# IO_FMU3_REV_C.net
KiCad netlist of a schematic drawn in Altium Designer
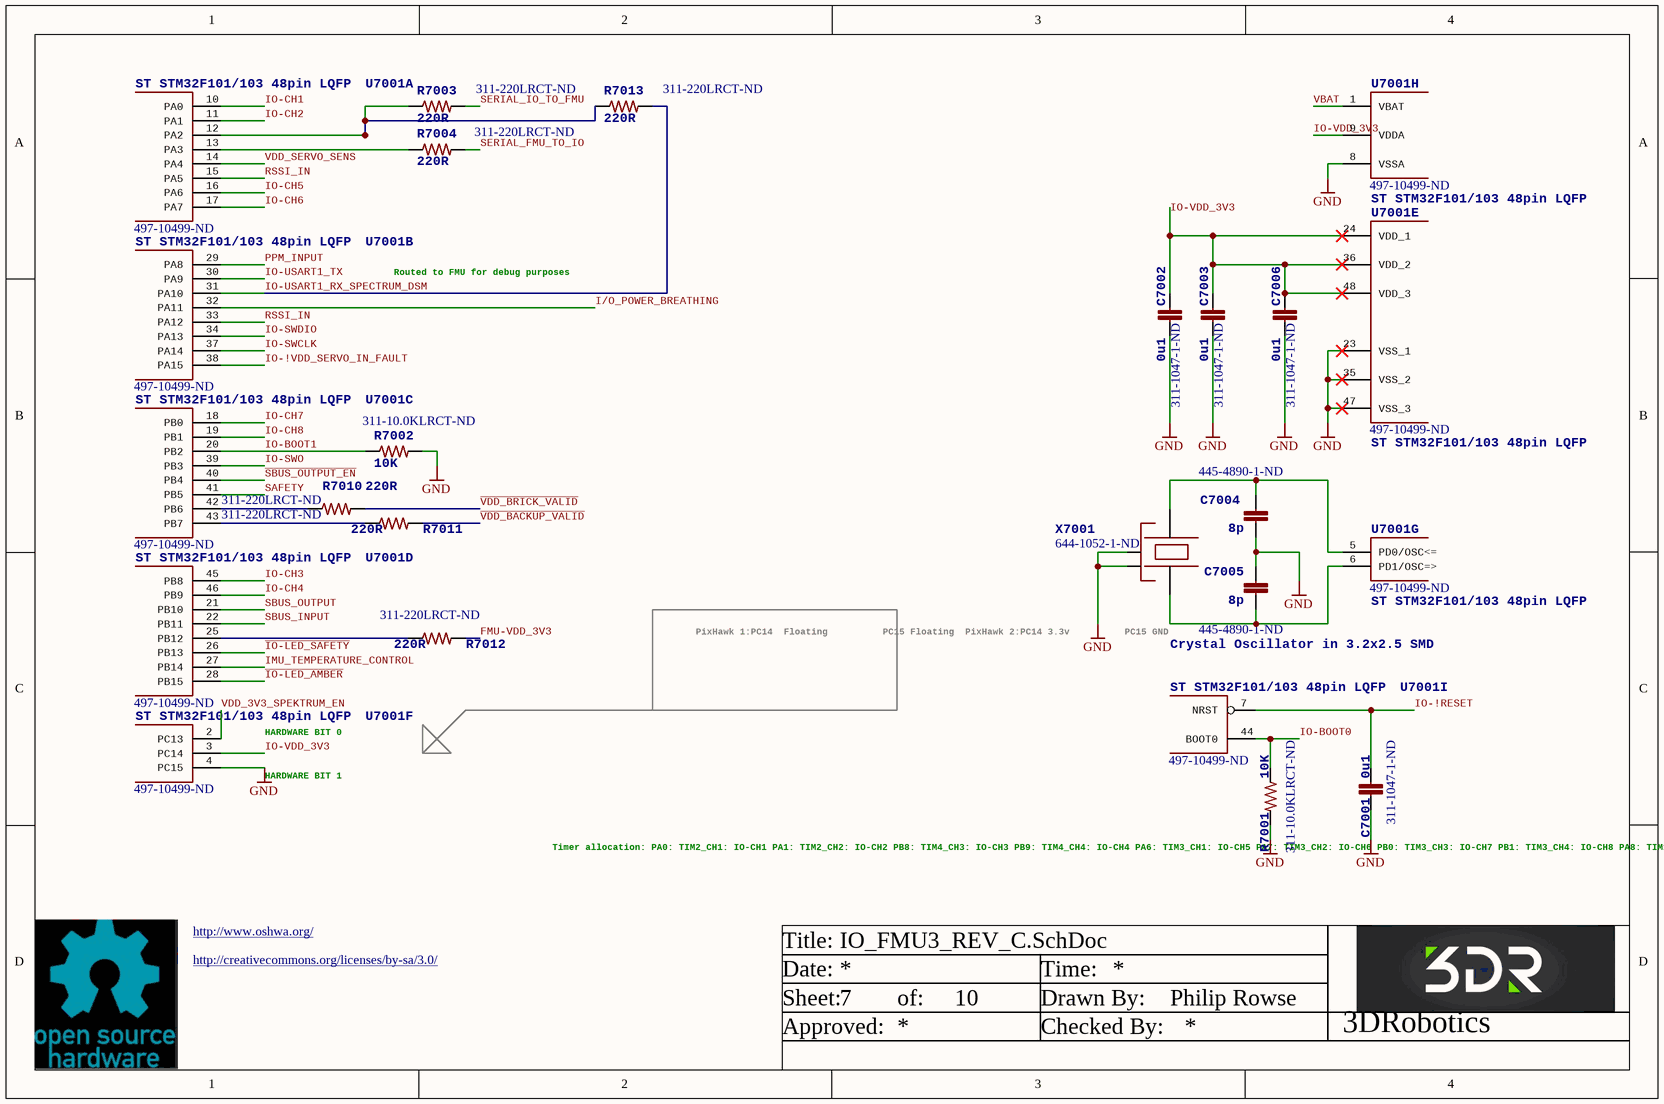
[diagram p0: IO_FMU3_REV_C.SchDoc]

(export (version "E")
  (design (tool "Eeschema 10.0.6"))
  (components
    (comp (ref "C7001")
      (value "0u1")
      (footprint "0402-CAP")
      (description "CAP CER 0.1UF 16V Y5V 0402")
      (fields
        (field (name "PARTNO") "CC0402ZRY5V7BB104")
        (field (name "SUPPLIER PART NUMBER 1") "311-1047-1-ND")
        (field (name "3DR_PARTNO") "ECM0700")
      )
      (libsource (lib "") (part "CAP0402_1"))
    )
    (comp (ref "C7002")
      (value "0u1")
      (footprint "0402-CAP")
      (description "CAP CER 0.1UF 16V Y5V 0402")
      (fields
        (field (name "PARTNO") "CC0402ZRY5V7BB104")
        (field (name "SUPPLIER PART NUMBER 1") "311-1047-1-ND")
        (field (name "3DR_PARTNO") "ECM0700")
      )
      (libsource (lib "pixhawk2") (part "CAP0402"))
    )
    (comp (ref "C7003")
      (value "0u1")
      (footprint "0402-CAP")
      (description "CAP CER 0.1UF 16V Y5V 0402")
      (fields
        (field (name "PARTNO") "CC0402ZRY5V7BB104")
        (field (name "SUPPLIER PART NUMBER 1") "311-1047-1-ND")
        (field (name "3DR_PARTNO") "ECM0700")
      )
      (libsource (lib "pixhawk2") (part "CAP0402"))
    )
    (comp (ref "C7004")
      (value "8p")
      (footprint "0402-CAP")
      (description "CAP CER 8PF 50V C0G 0402")
      (fields
        (field (name "PARTNO") "C1005C0G1H080C")
        (field (name "SUPPLIER PART NUMBER 1") "445-4890-1-ND")
        (field (name "3DR_PARTNO") "ECM0710")
      )
      (libsource (lib "pixhawk2") (part "CAP0402"))
    )
    (comp (ref "C7005")
      (value "8p")
      (footprint "0402-CAP")
      (description "CAP CER 8PF 50V C0G 0402")
      (fields
        (field (name "PARTNO") "C1005C0G1H080C")
        (field (name "SUPPLIER PART NUMBER 1") "445-4890-1-ND")
        (field (name "3DR_PARTNO") "ECM0710")
      )
      (libsource (lib "pixhawk2") (part "CAP0402"))
    )
    (comp (ref "C7006")
      (value "0u1")
      (footprint "0402-CAP")
      (description "CAP CER 0.1UF 16V Y5V 0402")
      (fields
        (field (name "PARTNO") "CC0402ZRY5V7BB104")
        (field (name "SUPPLIER PART NUMBER 1") "311-1047-1-ND")
        (field (name "3DR_PARTNO") "ECM0700")
      )
      (libsource (lib "pixhawk2") (part "CAP0402"))
    )
    (comp (ref "R7001")
      (value "10K")
      (footprint "0402-RES")
      (description "RES 10K OHM 1/16W 1% 0402 SMD")
      (fields
        (field (name "PARTNO") "RC0402FR-0710KL")
        (field (name "SUPPLIER PART NUMBER 1") "311-10.0KLRCT-ND")
        (field (name "3DR_PARTNO") "ECM0800")
      )
      (libsource (lib "pixhawk2") (part "RESISTOR0402-RES"))
    )
    (comp (ref "R7002")
      (value "10K")
      (footprint "0402-RES")
      (description "RES 10K OHM 1/16W 1% 0402 SMD")
      (fields
        (field (name "PARTNO") "RC0402FR-0710KL")
        (field (name "SUPPLIER PART NUMBER 1") "311-10.0KLRCT-ND")
        (field (name "3DR_PARTNO") "ECM0800")
      )
      (libsource (lib "pixhawk2") (part "RESISTOR0402-RES"))
    )
    (comp (ref "R7003")
      (value "220R")
      (footprint "0402-RES")
      (description "RES 220 OHM 1/16W 1% 0402 SMD")
      (fields
        (field (name "PARTNO") "RC0402FR-07220RL")
        (field (name "SUPPLIER PART NUMBER 1") "311-220LRCT-ND")
        (field (name "3DR_PARTNO") "ECM0821")
      )
      (libsource (lib "pixhawk2") (part "RESISTOR0402-RES"))
    )
    (comp (ref "R7004")
      (value "220R")
      (footprint "0402-RES")
      (description "RES 220 OHM 1/16W 1% 0402 SMD")
      (fields
        (field (name "PARTNO") "RC0402FR-07220RL")
        (field (name "SUPPLIER PART NUMBER 1") "311-220LRCT-ND")
        (field (name "3DR_PARTNO") "ECM0821")
      )
      (libsource (lib "pixhawk2") (part "RESISTOR0402-RES"))
    )
    (comp (ref "R7010")
      (value "220R")
      (footprint "0402-RES")
      (description "RES 220 OHM 1/16W 1% 0402 SMD")
      (fields
        (field (name "PARTNO") "RC0402FR-07220RL")
        (field (name "SUPPLIER PART NUMBER 1") "311-220LRCT-ND")
        (field (name "3DR_PARTNO") "ECM0821")
      )
      (libsource (lib "pixhawk2") (part "RESISTOR0402-RES"))
    )
    (comp (ref "R7011")
      (value "220R")
      (footprint "0402-RES")
      (description "RES 220 OHM 1/16W 1% 0402 SMD")
      (fields
        (field (name "PARTNO") "RC0402FR-07220RL")
        (field (name "SUPPLIER PART NUMBER 1") "311-220LRCT-ND")
        (field (name "3DR_PARTNO") "ECM0821")
      )
      (libsource (lib "pixhawk2") (part "RESISTOR0402-RES"))
    )
    (comp (ref "R7012")
      (value "220R")
      (footprint "0402-RES")
      (description "RES 220 OHM 1/16W 1% 0402 SMD")
      (fields
        (field (name "PARTNO") "RC0402FR-07220RL")
        (field (name "SUPPLIER PART NUMBER 1") "311-220LRCT-ND")
        (field (name "3DR_PARTNO") "ECM0821")
      )
      (libsource (lib "pixhawk2") (part "RESISTOR0402-RES"))
    )
    (comp (ref "R7013")
      (value "220R")
      (footprint "0402-RES")
      (description "RES 220 OHM 1/16W 1% 0402 SMD")
      (fields
        (field (name "PARTNO") "RC0402FR-07220RL")
        (field (name "SUPPLIER PART NUMBER 1") "311-220LRCT-ND")
        (field (name "3DR_PARTNO") "ECM0821")
      )
      (libsource (lib "pixhawk2") (part "RESISTOR0402-RES"))
    )
    (comp (ref "U7001")
      (value "ST STM32F101/103 48pin LQFP")
      (footprint "TQFP48")
      (description "MCU 32BIT ARM 64K FLASH 48LQFP")
      (fields (field (name "SUPPLIER PART NUMBER 1") "497-10499-ND") (field (name "3DR_PARTNO") "EMC0842"))
      (libsource (lib "pixhawk2") (part "STM32F10XCXT6"))
    )
    (comp (ref "X7001")
      (value "Crystal Oscillator in 3.2x2.5 SMD")
      (footprint "OSCILLATOR-3.2X2.5")
      (description "CRYSTAL 24MHZ 8PF SMD")
      (fields
        (field (name "SUPPLIER PART NUMBER 1") "644-1052-1-ND")
        (field (name "3DR_PARTNO") "ECM0708")
        (field (name "PARTNO") "NX3225SA-24.000MHZ-STD-CSR-1")
      )
      (libsource (lib "pixhawk2") (part "OSCILLATOR-3.2X2.5"))
    )
  )
  (nets
    (net (code "1") (name "/FMU-VDD_3V3") (class "Default")
      (node (ref "R7012") (pin "P$2") (pinfunction "2_P$2") (pintype "passive"))
    )
    (net (code "2") (name "/IMU_TEMPERATURE_CONTROL") (class "Default")
      (node (ref "U7001") (pin "27") (pinfunction "PB14_27") (pintype "passive"))
    )
    (net (code "3") (name "/IO-!RESET") (class "Default")
      (node (ref "C7001") (pin "P$2") (pinfunction "2_P$2") (pintype "passive"))
      (node (ref "U7001") (pin "7") (pinfunction "NRST_7") (pintype "passive"))
    )
    (net (code "4") (name "/IO-!VDD_SERVO_IN_FAULT") (class "Default")
      (node (ref "U7001") (pin "38") (pinfunction "PA15_38") (pintype "passive"))
    )
    (net (code "5") (name "/IO-BOOT0") (class "Default")
      (node (ref "R7001") (pin "P$1") (pinfunction "1_P$1") (pintype "passive"))
      (node (ref "U7001") (pin "44") (pinfunction "BOOT0_44") (pintype "passive"))
    )
    (net (code "6") (name "/IO-BOOT1") (class "Default")
      (node (ref "R7002") (pin "P$1") (pinfunction "1_P$1") (pintype "passive"))
      (node (ref "U7001") (pin "20") (pinfunction "PB2_20") (pintype "passive"))
    )
    (net (code "7") (name "/IO-CH1") (class "Default")
      (node (ref "U7001") (pin "10") (pinfunction "PA0_10") (pintype "passive"))
    )
    (net (code "8") (name "/IO-CH2") (class "Default")
      (node (ref "U7001") (pin "11") (pinfunction "PA1_11") (pintype "passive"))
    )
    (net (code "9") (name "/IO-CH3") (class "Default")
      (node (ref "U7001") (pin "45") (pinfunction "PB8_45") (pintype "passive"))
    )
    (net (code "10") (name "/IO-CH4") (class "Default")
      (node (ref "U7001") (pin "46") (pinfunction "PB9_46") (pintype "passive"))
    )
    (net (code "11") (name "/IO-CH5") (class "Default")
      (node (ref "U7001") (pin "16") (pinfunction "PA6_16") (pintype "passive"))
    )
    (net (code "12") (name "/IO-CH6") (class "Default")
      (node (ref "U7001") (pin "17") (pinfunction "PA7_17") (pintype "passive"))
    )
    (net (code "13") (name "/IO-CH7") (class "Default")
      (node (ref "U7001") (pin "18") (pinfunction "PB0_18") (pintype "passive"))
    )
    (net (code "14") (name "/IO-CH8") (class "Default")
      (node (ref "U7001") (pin "19") (pinfunction "PB1_19") (pintype "passive"))
    )
    (net (code "15") (name "/IO-SWCLK") (class "Default")
      (node (ref "U7001") (pin "37") (pinfunction "PA14_37") (pintype "passive"))
    )
    (net (code "16") (name "/IO-SWDIO") (class "Default")
      (node (ref "U7001") (pin "34") (pinfunction "PA13_34") (pintype "passive"))
    )
    (net (code "17") (name "/IO-SWO") (class "Default")
      (node (ref "U7001") (pin "39") (pinfunction "PB3_39") (pintype "passive"))
    )
    (net (code "18") (name "/IO-USART1_RX_SPECTRUM_DSM") (class "Default")
      (node (ref "R7013") (pin "P$2") (pinfunction "2_P$2") (pintype "passive"))
      (node (ref "U7001") (pin "31") (pinfunction "PA10_31") (pintype "passive"))
    )
    (net (code "19") (name "/IO-USART1_TX") (class "Default")
      (node (ref "U7001") (pin "30") (pinfunction "PA9_30") (pintype "passive"))
    )
    (net (code "20") (name "/IO-VDD_3V3") (class "Default")
      (node (ref "C7002") (pin "P$1") (pinfunction "1_P$1") (pintype "passive"))
      (node (ref "C7003") (pin "P$1") (pinfunction "1_P$1") (pintype "passive"))
      (node (ref "C7006") (pin "P$1") (pinfunction "1_P$1") (pintype "passive"))
      (node (ref "U7001") (pin "24") (pinfunction "VDD_1_24") (pintype "power_in"))
      (node (ref "U7001") (pin "3") (pinfunction "PC14_3") (pintype "passive"))
      (node (ref "U7001") (pin "36") (pinfunction "VDD_2_36") (pintype "power_in"))
      (node (ref "U7001") (pin "48") (pinfunction "VDD_3_48") (pintype "power_in"))
      (node (ref "U7001") (pin "9") (pinfunction "VDDA_9") (pintype "power_in"))
    )
    (net (code "21") (name "/I{slash}O_POWER_BREATHING") (class "Default")
      (node (ref "U7001") (pin "32") (pinfunction "PA11_32") (pintype "passive"))
    )
    (net (code "22") (name "/PPM_INPUT") (class "Default")
      (node (ref "U7001") (pin "29") (pinfunction "PA8_29") (pintype "passive"))
    )
    (net (code "23") (name "/RSSI_IN") (class "Default")
      (node (ref "U7001") (pin "15") (pinfunction "PA5_15") (pintype "passive"))
      (node (ref "U7001") (pin "33") (pinfunction "PA12_33") (pintype "passive"))
    )
    (net (code "24") (name "/SAFETY") (class "Default")
      (node (ref "U7001") (pin "41") (pinfunction "PB5_41") (pintype "passive"))
    )
    (net (code "25") (name "/SBUS_INPUT") (class "Default")
      (node (ref "U7001") (pin "22") (pinfunction "PB11_22") (pintype "passive"))
    )
    (net (code "26") (name "/SBUS_OUTPUT") (class "Default")
      (node (ref "U7001") (pin "21") (pinfunction "PB10_21") (pintype "passive"))
    )
    (net (code "27") (name "/SERIAL_FMU_TO_IO") (class "Default")
      (node (ref "R7004") (pin "P$2") (pinfunction "2_P$2") (pintype "passive"))
    )
    (net (code "28") (name "/SERIAL_IO_TO_FMU") (class "Default")
      (node (ref "R7003") (pin "P$2") (pinfunction "2_P$2") (pintype "passive"))
    )
    (net (code "29") (name "/VBAT") (class "Default")
      (node (ref "U7001") (pin "1") (pinfunction "VBAT_1") (pintype "power_in"))
    )
    (net (code "30") (name "/VDD_3V3_SPEKTRUM_EN") (class "Default")
      (node (ref "U7001") (pin "2") (pinfunction "PC13_2") (pintype "passive"))
    )
    (net (code "31") (name "/VDD_SERVO_SENS") (class "Default")
      (node (ref "U7001") (pin "14") (pinfunction "PA4_14") (pintype "passive"))
    )
    (net (code "32") (name "/~{IO-LED_AMBER}") (class "Default")
      (node (ref "U7001") (pin "28") (pinfunction "PB15_28") (pintype "passive"))
    )
    (net (code "33") (name "/~{IO-LED_SAFETY}") (class "Default")
      (node (ref "U7001") (pin "26") (pinfunction "PB13_26") (pintype "passive"))
    )
    (net (code "34") (name "/~{SBUS_OUTPUT_EN}") (class "Default")
      (node (ref "U7001") (pin "40") (pinfunction "PB4_40") (pintype "passive"))
    )
    (net (code "35") (name "/~{VDD_BACKUP_VALID}") (class "Default")
      (node (ref "R7011") (pin "P$2") (pinfunction "2_P$2") (pintype "passive"))
    )
    (net (code "36") (name "/~{VDD_BRICK_VALID}") (class "Default")
      (node (ref "R7010") (pin "P$2") (pinfunction "2_P$2") (pintype "passive"))
    )
    (net (code "37") (name "GND") (class "Default")
      (node (ref "C7001") (pin "P$1") (pinfunction "1_P$1") (pintype "passive"))
      (node (ref "C7002") (pin "P$2") (pinfunction "2_P$2") (pintype "passive"))
      (node (ref "C7003") (pin "P$2") (pinfunction "2_P$2") (pintype "passive"))
      (node (ref "C7004") (pin "P$2") (pinfunction "2_P$2") (pintype "passive"))
      (node (ref "C7005") (pin "P$1") (pinfunction "1_P$1") (pintype "passive"))
      (node (ref "C7006") (pin "P$2") (pinfunction "2_P$2") (pintype "passive"))
      (node (ref "R7001") (pin "P$2") (pinfunction "2_P$2") (pintype "passive"))
      (node (ref "R7002") (pin "P$2") (pinfunction "2_P$2") (pintype "passive"))
      (node (ref "U7001") (pin "23") (pinfunction "VSS_1_23") (pintype "power_in"))
      (node (ref "U7001") (pin "35") (pinfunction "VSS_2_35") (pintype "power_in"))
      (node (ref "U7001") (pin "4") (pinfunction "PC15_4") (pintype "passive"))
      (node (ref "U7001") (pin "47") (pinfunction "VSS_3_47") (pintype "power_in"))
      (node (ref "U7001") (pin "8") (pinfunction "VSSA_8") (pintype "power_in"))
      (node (ref "X7001") (pin "2") (pinfunction "NC_2_2") (pintype "open_emitter"))
      (node (ref "X7001") (pin "4") (pinfunction "NC_4_4") (pintype "open_emitter"))
    )
    (net (code "38") (name "Net-(C7004-1)") (class "Default")
      (node (ref "C7004") (pin "P$1") (pinfunction "1_P$1") (pintype "passive"))
      (node (ref "U7001") (pin "5") (pinfunction "PD0/OSC<=_5") (pintype "passive"))
      (node (ref "X7001") (pin "3") (pinfunction "3_3") (pintype "passive"))
    )
    (net (code "39") (name "Net-(C7005-2)") (class "Default")
      (node (ref "C7005") (pin "P$2") (pinfunction "2_P$2") (pintype "passive"))
      (node (ref "U7001") (pin "6") (pinfunction "PD1/OSC=>_6") (pintype "passive"))
      (node (ref "X7001") (pin "1") (pinfunction "1_1") (pintype "passive"))
    )
    (net (code "40") (name "Net-(R7003-1)") (class "Default")
      (node (ref "R7003") (pin "P$1") (pinfunction "1_P$1") (pintype "passive"))
      (node (ref "R7013") (pin "P$1") (pinfunction "1_P$1") (pintype "passive"))
      (node (ref "U7001") (pin "12") (pinfunction "PA2_12") (pintype "passive"))
    )
    (net (code "41") (name "Net-(R7004-1)") (class "Default")
      (node (ref "R7004") (pin "P$1") (pinfunction "1_P$1") (pintype "passive"))
      (node (ref "U7001") (pin "13") (pinfunction "PA3_13") (pintype "passive"))
    )
    (net (code "42") (name "Net-(R7010-1)") (class "Default")
      (node (ref "R7010") (pin "P$1") (pinfunction "1_P$1") (pintype "passive"))
      (node (ref "U7001") (pin "42") (pinfunction "PB6_42") (pintype "passive"))
    )
    (net (code "43") (name "Net-(R7011-1)") (class "Default")
      (node (ref "R7011") (pin "P$1") (pinfunction "1_P$1") (pintype "passive"))
      (node (ref "U7001") (pin "43") (pinfunction "PB7_43") (pintype "passive"))
    )
    (net (code "44") (name "Net-(R7012-1)") (class "Default")
      (node (ref "R7012") (pin "P$1") (pinfunction "1_P$1") (pintype "passive"))
      (node (ref "U7001") (pin "25") (pinfunction "PB12_25") (pintype "passive"))
    )
  )
)
